# OK10xx_S_V1_1.net
KiCad netlist of a schematic drawn in Altium Designer
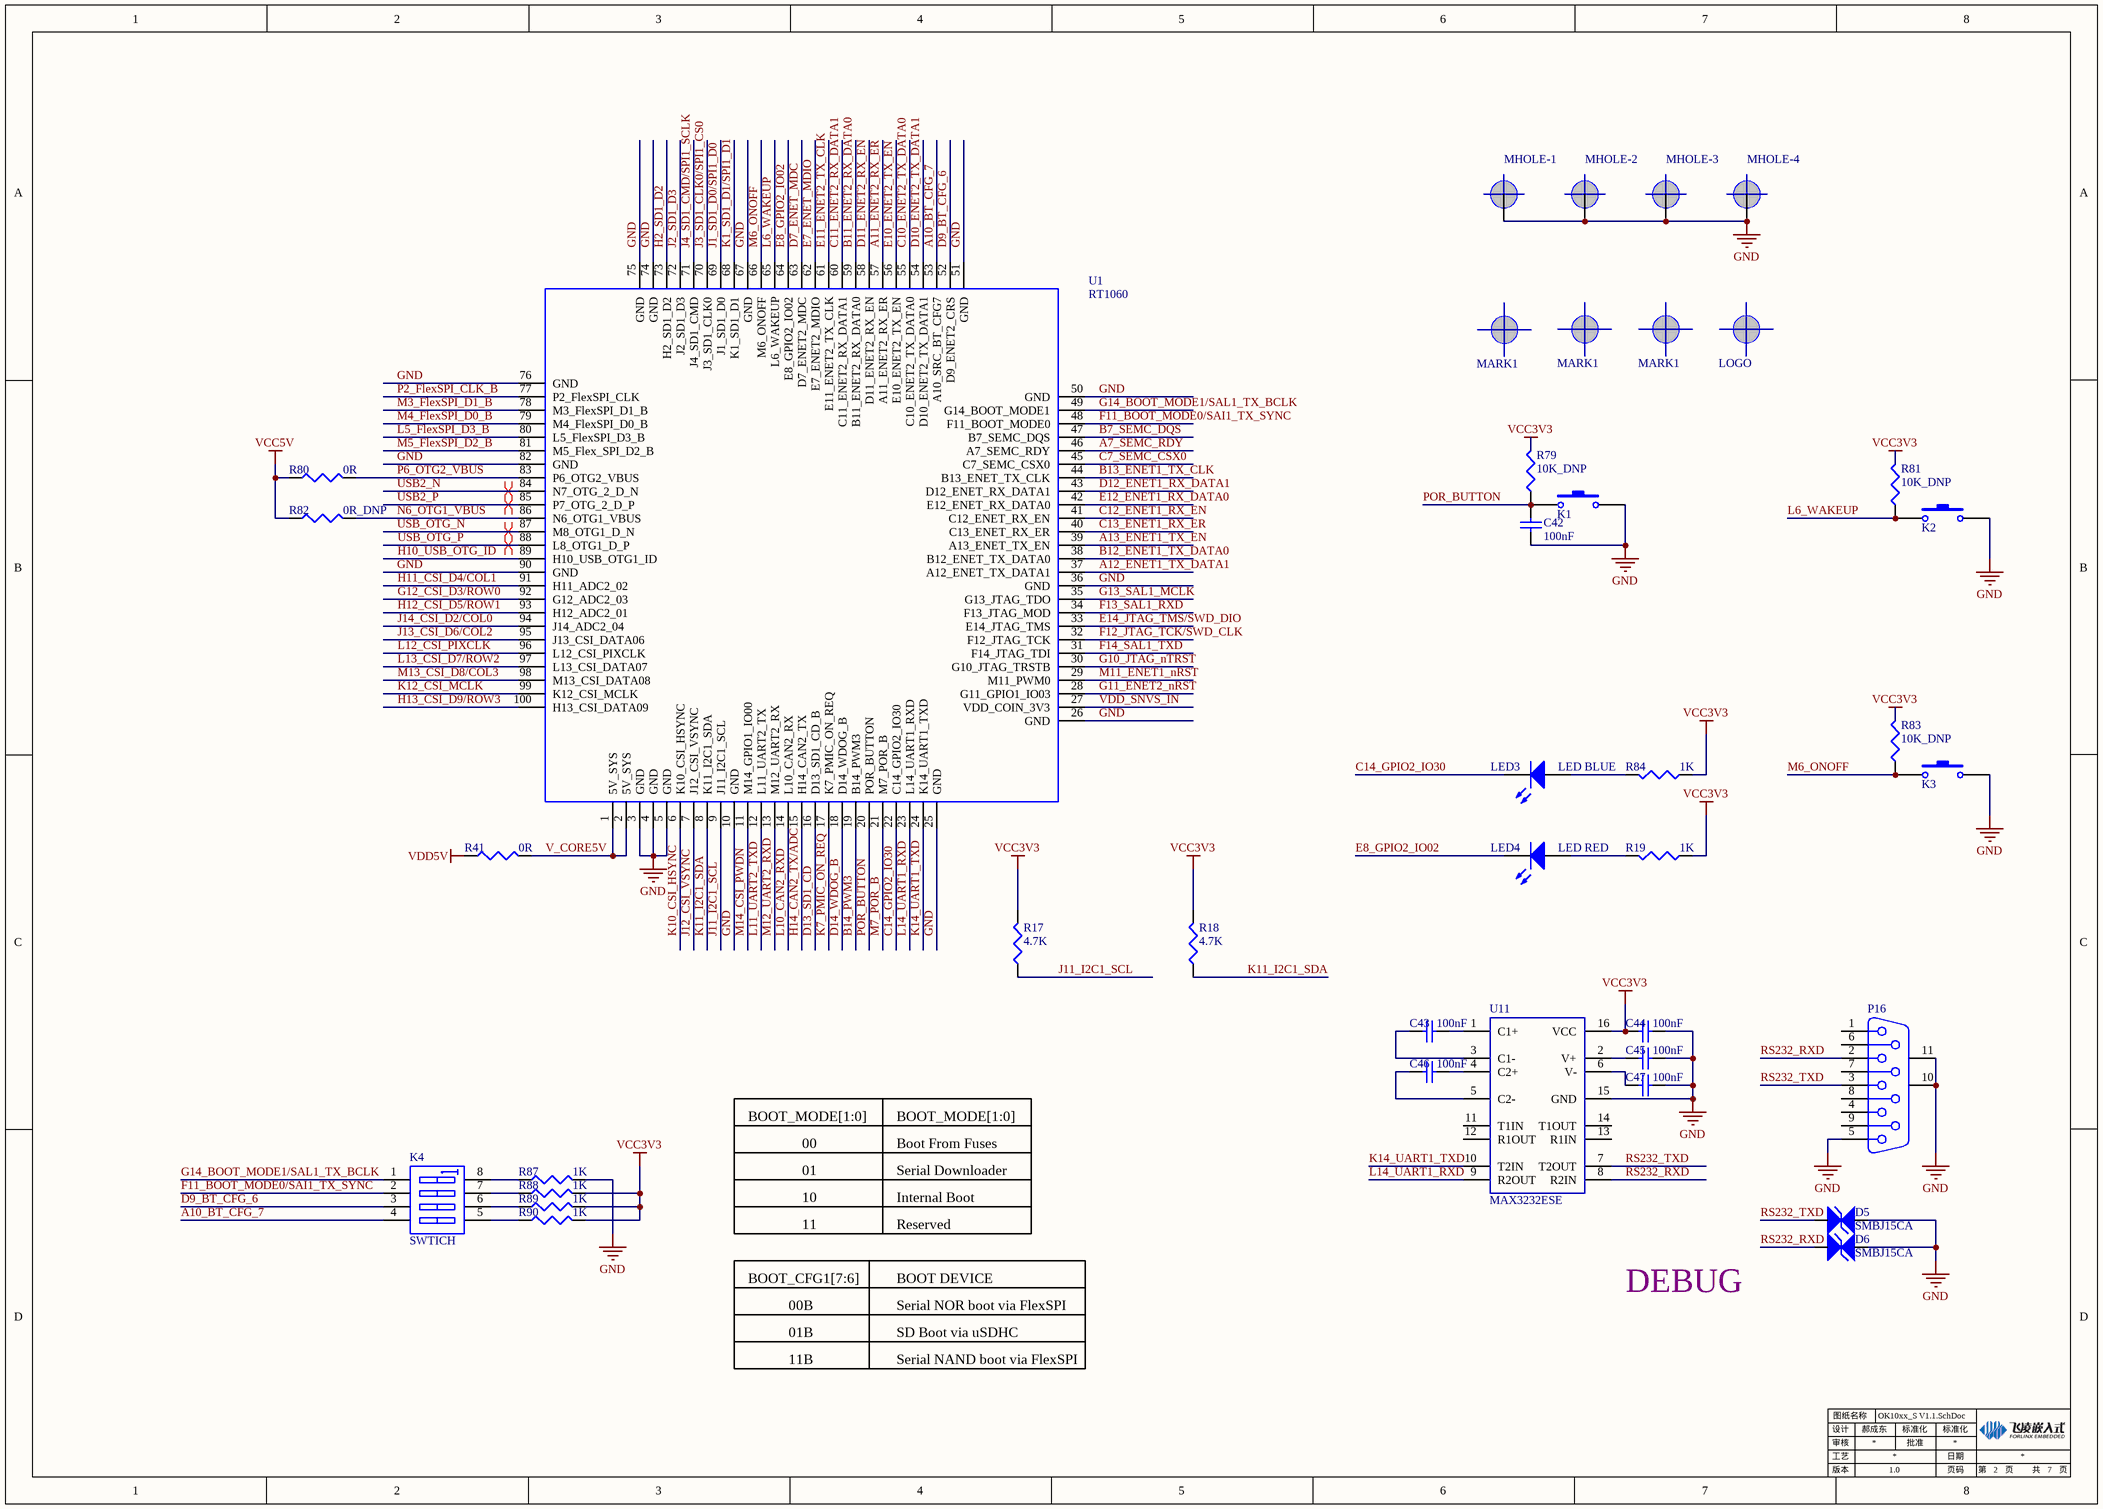
[diagram p0: OK10xx_S V1.1.SchDoc]

(export (version "E")
  (design (tool "Eeschema 10.0.6"))
  (components
    (comp (ref "C42")
      (value "100nF")
      (footprint "0603C+")
      (description "Capacitor")
      (fields (field (name "PUBLISHER") "Altium Limited"))
      (libsource (lib "RT1060") (part "Cap"))
    )
    (comp (ref "C43")
      (value "100nF")
      (footprint "0603C+")
      (description "Capacitor")
      (fields (field (name "PUBLISHER") "Altium Limited"))
      (libsource (lib "Miscellaneous Devices") (part "Cap"))
    )
    (comp (ref "C44")
      (value "100nF")
      (footprint "0603C+")
      (description "Capacitor")
      (fields (field (name "PUBLISHER") "Altium Limited"))
      (libsource (lib "Miscellaneous Devices") (part "Cap"))
    )
    (comp (ref "C45")
      (value "100nF")
      (footprint "0603C+")
      (description "Capacitor")
      (fields (field (name "PUBLISHER") "Altium Limited"))
      (libsource (lib "Miscellaneous Devices") (part "Cap"))
    )
    (comp (ref "C46")
      (value "100nF")
      (footprint "0603C+")
      (description "Capacitor")
      (fields (field (name "PUBLISHER") "Altium Limited"))
      (libsource (lib "Miscellaneous Devices") (part "Cap"))
    )
    (comp (ref "C47")
      (value "100nF")
      (footprint "0603C+")
      (description "Capacitor")
      (fields (field (name "PUBLISHER") "Altium Limited"))
      (libsource (lib "Miscellaneous Devices") (part "Cap"))
    )
    (comp (ref "D5") (value "SMBJ15CA") (footprint "SMB/DO-214AA") (libsource (lib "RT1060") (part "TVS")))
    (comp (ref "D6") (value "SMBJ15CA") (footprint "SMB/DO-214AA") (libsource (lib "RT1060") (part "TVS")))
    (comp (ref "K1")
      (value "6*6*5侧位2脚带支架")
      (description "Switch")
      (fields (field (name "PUBLISHER") "Altium Limited"))
      (libsource (lib "RT1060") (part "SW-PB"))
    )
    (comp (ref "K2")
      (value "6*6*5侧位2脚带支架")
      (description "Switch")
      (fields (field (name "PUBLISHER") "Altium Limited"))
      (libsource (lib "RT1060") (part "SW-PB"))
    )
    (comp (ref "K3")
      (value "6*6*5侧位2脚带支架")
      (description "Switch")
      (fields (field (name "PUBLISHER") "Altium Limited"))
      (libsource (lib "RT1060") (part "SW-PB"))
    )
    (comp (ref "K4") (value "SWTICH") (footprint "SMD_4") (libsource (lib "RT1060") (part "SWTICH_DIP6")))
    (comp (ref "LED3")
      (value "LED_BULE")
      (footprint "LED0603_M1608")
      (description "Typical RED, GREEN, YELLOW, AMBER GaAs LED")
      (fields (field (name "BOOK") "LED BLUE") (field (name "PUBLISHER") "Altium Limited"))
      (libsource (lib "RT1060") (part "LED2"))
    )
    (comp (ref "LED4")
      (value "LED_BULE")
      (footprint "LED0603_M1608")
      (description "Typical RED, GREEN, YELLOW, AMBER GaAs LED")
      (fields (field (name "BOOK") "LED RED") (field (name "PUBLISHER") "Altium Limited"))
      (libsource (lib "RT1060") (part "LED2"))
    )
    (comp (ref "LOGO1") (value "LOGO") (footprint "LOGO") (libsource (lib "RT1060") (part "MHOLE_1")))
    (comp (ref "M1") (value "MHOLE-1") (footprint "3.2mm_hole") (libsource (lib "RT1060") (part "MHOLE-2")))
    (comp (ref "M2") (value "MHOLE-2") (footprint "3.2mm_hole") (libsource (lib "RT1060") (part "MHOLE-2")))
    (comp (ref "M3") (value "MHOLE-3") (footprint "3.2mm_hole") (libsource (lib "RT1060") (part "MHOLE-2")))
    (comp (ref "M4") (value "MHOLE-4") (footprint "3.2mm_hole") (libsource (lib "RT1060") (part "MHOLE-2")))
    (comp (ref "Mark1") (value "MARK1") (footprint "MARK POINT") (libsource (lib "RT1060") (part "MHOLE")))
    (comp (ref "Mark2") (value "MARK1") (footprint "MARK POINT") (libsource (lib "RT1060") (part "MHOLE")))
    (comp (ref "Mark3") (value "MARK1") (footprint "MARK POINT") (libsource (lib "RT1060") (part "MHOLE")))
    (comp (ref "P16")
      (value "DEBUG")
      (footprint "DSUB1.385-2H9-M")
      (description "Receptacle Assembly, 9 Position, Right Angle")
      (fields (field (name "PUBLISHER") "Altium Limited"))
      (libsource (lib "RT1060") (part "D Connector 9"))
    )
    (comp (ref "R17")
      (value "4.7K")
      (footprint "0603R+")
      (description "Resistor")
      (fields (field (name "PUBLISHER") "Altium Limited"))
      (libsource (lib "Miscellaneous Devices") (part "Res3"))
    )
    (comp (ref "R18")
      (value "4.7K")
      (footprint "0603R+")
      (description "Resistor")
      (fields (field (name "PUBLISHER") "Altium Limited"))
      (libsource (lib "Miscellaneous Devices") (part "Res3"))
    )
    (comp (ref "R19")
      (value "1K")
      (footprint "0603R+")
      (description "Resistor")
      (fields (field (name "PUBLISHER") "Altium Limited"))
      (libsource (lib "RT1060") (part "Res3"))
    )
    (comp (ref "R41")
      (value "0R")
      (footprint "R_1210")
      (description "Resistor")
      (fields (field (name "PUBLISHER") "Altium Limited"))
      (libsource (lib "RT1060") (part "Res3"))
    )
    (comp (ref "R79")
      (value "10K_DNP")
      (footprint "0603R+")
      (description "Resistor")
      (fields (field (name "PUBLISHER") "Altium Limited"))
      (libsource (lib "RT1060") (part "Res3"))
    )
    (comp (ref "R80")
      (value "0R")
      (footprint "0603R+")
      (description "Resistor")
      (fields (field (name "PUBLISHER") "Altium Limited"))
      (libsource (lib "RT1060") (part "Res3"))
    )
    (comp (ref "R81")
      (value "10K_DNP")
      (footprint "0603R+")
      (description "Resistor")
      (fields (field (name "PUBLISHER") "Altium Limited"))
      (libsource (lib "RT1060") (part "Res3"))
    )
    (comp (ref "R82")
      (value "0R_DNP")
      (footprint "0603R+")
      (description "Resistor")
      (fields (field (name "PUBLISHER") "Altium Limited"))
      (libsource (lib "RT1060") (part "Res3"))
    )
    (comp (ref "R83")
      (value "10K_DNP")
      (footprint "0603R+")
      (description "Resistor")
      (fields (field (name "PUBLISHER") "Altium Limited"))
      (libsource (lib "RT1060") (part "Res3"))
    )
    (comp (ref "R84")
      (value "1K")
      (footprint "0603R+")
      (description "Resistor")
      (fields (field (name "PUBLISHER") "Altium Limited"))
      (libsource (lib "RT1060") (part "Res3"))
    )
    (comp (ref "R87")
      (value "1K")
      (footprint "0603R+")
      (description "Resistor")
      (fields (field (name "PUBLISHER") "Altium Limited"))
      (libsource (lib "RT1060") (part "Res3"))
    )
    (comp (ref "R88")
      (value "1K")
      (footprint "0603R+")
      (description "Resistor")
      (fields (field (name "PUBLISHER") "Altium Limited"))
      (libsource (lib "RT1060") (part "Res3"))
    )
    (comp (ref "R89")
      (value "1K")
      (footprint "0603R+")
      (description "Resistor")
      (fields (field (name "PUBLISHER") "Altium Limited"))
      (libsource (lib "RT1060") (part "Res3"))
    )
    (comp (ref "R90")
      (value "1K")
      (footprint "0603R+")
      (description "Resistor")
      (fields (field (name "PUBLISHER") "Altium Limited"))
      (libsource (lib "RT1060") (part "Res3"))
    )
    (comp (ref "U1") (value "RT1060") (libsource (lib "RT1060") (part "RT1060")))
    (comp (ref "U11") (value "MAX3232ESE") (footprint "SOIC-16N") (libsource (lib "RT1060") (part "MAX3232")))
  )
  (nets
    (net (code "1") (name "/A7_SEMC_RDY") (class "Default")
      (node (ref "U1") (pin "46") (pinfunction "A7_SEMC_RDY_46") (pintype "passive"))
    )
    (net (code "2") (name "/A10_BT_CFG_7") (class "Default")
      (node (ref "K4") (pin "4") (pinfunction "A4_4") (pintype "passive"))
      (node (ref "U1") (pin "53") (pinfunction "A10_SRC_BT_CFG7_53") (pintype "passive"))
    )
    (net (code "3") (name "/A11_ENET2_RX_ER") (class "Default")
      (node (ref "U1") (pin "57") (pinfunction "A11_ENET2_RX_ER_57") (pintype "passive"))
    )
    (net (code "4") (name "/A12_ENET1_TX_DATA1") (class "Default")
      (node (ref "U1") (pin "37") (pinfunction "A12_ENET_TX_DATA1_37") (pintype "passive"))
    )
    (net (code "5") (name "/A13_ENET1_TX_EN") (class "Default")
      (node (ref "U1") (pin "39") (pinfunction "A13_ENET_TX_EN_39") (pintype "passive"))
    )
    (net (code "6") (name "/B7_SEMC_DQS") (class "Default")
      (node (ref "U1") (pin "47") (pinfunction "B7_SEMC_DQS_47") (pintype "passive"))
    )
    (net (code "7") (name "/B11_ENET2_RX_DATA0") (class "Default")
      (node (ref "U1") (pin "59") (pinfunction "B11_ENET2_RX_DATA0_59") (pintype "passive"))
    )
    (net (code "8") (name "/B12_ENET1_TX_DATA0") (class "Default")
      (node (ref "U1") (pin "38") (pinfunction "B12_ENET_TX_DATA0_38") (pintype "passive"))
    )
    (net (code "9") (name "/B13_ENET1_TX_CLK") (class "Default")
      (node (ref "U1") (pin "44") (pinfunction "B13_ENET_TX_CLK_44") (pintype "passive"))
    )
    (net (code "10") (name "/B14_PWM3") (class "Default")
      (node (ref "U1") (pin "19") (pinfunction "B14_PWM3_19") (pintype "passive"))
    )
    (net (code "11") (name "/C7_SEMC_CSX0") (class "Default")
      (node (ref "U1") (pin "45") (pinfunction "C7_SEMC_CSX0_45") (pintype "passive"))
    )
    (net (code "12") (name "/C10_ENET2_TX_DATA0") (class "Default")
      (node (ref "U1") (pin "55") (pinfunction "C10_ENET2_TX_DATA0_55") (pintype "passive"))
    )
    (net (code "13") (name "/C11_ENET2_RX_DATA1") (class "Default")
      (node (ref "U1") (pin "60") (pinfunction "C11_ENET2_RX_DATA1_60") (pintype "passive"))
    )
    (net (code "14") (name "/C12_ENET1_RX_EN") (class "Default")
      (node (ref "U1") (pin "41") (pinfunction "C12_ENET_RX_EN_41") (pintype "passive"))
    )
    (net (code "15") (name "/C13_ENET1_RX_ER") (class "Default")
      (node (ref "U1") (pin "40") (pinfunction "C13_ENET_RX_ER_40") (pintype "passive"))
    )
    (net (code "16") (name "/C14_GPIO2_IO30") (class "Default")
      (node (ref "LED3") (pin "2") (pinfunction "K_2") (pintype "passive"))
      (node (ref "U1") (pin "22") (pinfunction "C14_GPIO2_IO30_22") (pintype "passive"))
    )
    (net (code "17") (name "/D7_ENET_MDC") (class "Default")
      (node (ref "U1") (pin "63") (pinfunction "D7_ENET2_MDC_63") (pintype "passive"))
    )
    (net (code "18") (name "/D9_BT_CFG_6") (class "Default")
      (node (ref "K4") (pin "3") (pinfunction "A3_3") (pintype "passive"))
      (node (ref "U1") (pin "52") (pinfunction "D9_ENET2_CRS_52") (pintype "passive"))
    )
    (net (code "19") (name "/D10_ENET2_TX_DATA1") (class "Default")
      (node (ref "U1") (pin "54") (pinfunction "D10_ENET2_TX_DATA1_54") (pintype "passive"))
    )
    (net (code "20") (name "/D11_ENET2_RX_EN") (class "Default")
      (node (ref "U1") (pin "58") (pinfunction "D11_ENET2_RX_EN_58") (pintype "passive"))
    )
    (net (code "21") (name "/D12_ENET1_RX_DATA1") (class "Default")
      (node (ref "U1") (pin "43") (pinfunction "D12_ENET_RX_DATA1_43") (pintype "passive"))
    )
    (net (code "22") (name "/D13_SD1_CD") (class "Default")
      (node (ref "U1") (pin "16") (pinfunction "D13_SD1_CD_B_16") (pintype "passive"))
    )
    (net (code "23") (name "/D14_WDOG_B") (class "Default")
      (node (ref "U1") (pin "18") (pinfunction "D14_WDOG_B_18") (pintype "passive"))
    )
    (net (code "24") (name "/E7_ENET_MDIO") (class "Default")
      (node (ref "U1") (pin "62") (pinfunction "E7_ENET2_MDIO_62") (pintype "passive"))
    )
    (net (code "25") (name "/E8_GPIO2_IO02") (class "Default")
      (node (ref "LED4") (pin "2") (pinfunction "K_2") (pintype "passive"))
      (node (ref "U1") (pin "64") (pinfunction "E8_GPIO2_IO02_64") (pintype "passive"))
    )
    (net (code "26") (name "/E10_ENET2_TX_EN") (class "Default")
      (node (ref "U1") (pin "56") (pinfunction "E10_ENET2_TX_EN_56") (pintype "passive"))
    )
    (net (code "27") (name "/E11_ENET2_TX_CLK") (class "Default")
      (node (ref "U1") (pin "61") (pinfunction "E11_ENET2_TX_CLK_61") (pintype "passive"))
    )
    (net (code "28") (name "/E12_ENET1_RX_DATA0") (class "Default")
      (node (ref "U1") (pin "42") (pinfunction "E12_ENET_RX_DATA0_42") (pintype "passive"))
    )
    (net (code "29") (name "/E14_JTAG_TMS{slash}SWD_DIO") (class "Default")
      (node (ref "U1") (pin "33") (pinfunction "E14_JTAG_TMS_33") (pintype "passive"))
    )
    (net (code "30") (name "/F11_BOOT_MODE0{slash}SAI1_TX_SYNC") (class "Default")
      (node (ref "K4") (pin "2") (pinfunction "A2_2") (pintype "passive"))
      (node (ref "U1") (pin "48") (pinfunction "F11_BOOT_MODE0_48") (pintype "passive"))
    )
    (net (code "31") (name "/F12_JTAG_TCK{slash}SWD_CLK") (class "Default")
      (node (ref "U1") (pin "32") (pinfunction "F12_JTAG_TCK_32") (pintype "passive"))
    )
    (net (code "32") (name "/F13_SAL1_RXD") (class "Default")
      (node (ref "U1") (pin "34") (pinfunction "F13_JTAG_MOD_34") (pintype "passive"))
    )
    (net (code "33") (name "/F14_SAL1_TXD") (class "Default")
      (node (ref "U1") (pin "31") (pinfunction "F14_JTAG_TDI_31") (pintype "passive"))
    )
    (net (code "34") (name "/G10_JTAG_nTRST") (class "Default")
      (node (ref "U1") (pin "30") (pinfunction "G10_JTAG_TRSTB_30") (pintype "passive"))
    )
    (net (code "35") (name "/G11_ENET2_nRST") (class "Default")
      (node (ref "U1") (pin "28") (pinfunction "G11_GPIO1_IO03_28") (pintype "passive"))
    )
    (net (code "36") (name "/G12_CSI_D3{slash}ROW0") (class "Default")
      (node (ref "U1") (pin "92") (pinfunction "G12_ADC2_03_92") (pintype "passive"))
    )
    (net (code "37") (name "/G13_SAL1_MCLK") (class "Default")
      (node (ref "U1") (pin "35") (pinfunction "G13_JTAG_TDO_35") (pintype "passive"))
    )
    (net (code "38") (name "/G14_BOOT_MODE1{slash}SAL1_TX_BCLK") (class "Default")
      (node (ref "K4") (pin "1") (pinfunction "A1_1") (pintype "passive"))
      (node (ref "U1") (pin "49") (pinfunction "G14_BOOT_MODE1_49") (pintype "passive"))
    )
    (net (code "39") (name "/H2_SD1_D2") (class "Default")
      (node (ref "U1") (pin "73") (pinfunction "H2_SD1_D2_73") (pintype "passive"))
    )
    (net (code "40") (name "/H10_USB_OTG_ID") (class "Default")
      (node (ref "U1") (pin "89") (pinfunction "H10_USB_OTG1_ID_89") (pintype "passive"))
    )
    (net (code "41") (name "/H11_CSI_D4{slash}COL1") (class "Default")
      (node (ref "U1") (pin "91") (pinfunction "H11_ADC2_02_91") (pintype "passive"))
    )
    (net (code "42") (name "/H12_CSI_D5{slash}ROW1") (class "Default")
      (node (ref "U1") (pin "93") (pinfunction "H12_ADC2_01_93") (pintype "passive"))
    )
    (net (code "43") (name "/H13_CSI_D9{slash}ROW3") (class "Default")
      (node (ref "U1") (pin "100") (pinfunction "H13_CSI_DATA09_100") (pintype "passive"))
    )
    (net (code "44") (name "/H14_CAN2_TX{slash}ADC") (class "Default")
      (node (ref "U1") (pin "15") (pinfunction "H14_CAN2_TX_15") (pintype "passive"))
    )
    (net (code "45") (name "/J1_SD1_D0{slash}SPI1_D0") (class "Default")
      (node (ref "U1") (pin "69") (pinfunction "J1_SD1_D0_69") (pintype "passive"))
    )
    (net (code "46") (name "/J2_SD1_D3") (class "Default")
      (node (ref "U1") (pin "72") (pinfunction "J2_SD1_D3_72") (pintype "passive"))
    )
    (net (code "47") (name "/J3_SD1_CLK0{slash}SPI1_CS0") (class "Default")
      (node (ref "U1") (pin "70") (pinfunction "J3_SD1_CLK0_70") (pintype "passive"))
    )
    (net (code "48") (name "/J4_SD1_CMD{slash}SPI1_SCLK") (class "Default")
      (node (ref "U1") (pin "71") (pinfunction "J4_SD1_CMD_71") (pintype "passive"))
    )
    (net (code "49") (name "/J11_I2C1_SCL") (class "Default")
      (node (ref "R17") (pin "1") (pinfunction "1_1") (pintype "passive"))
      (node (ref "U1") (pin "9") (pinfunction "J11_I2C1_SCL_9") (pintype "passive"))
    )
    (net (code "50") (name "/J12_CSI_VSYNC") (class "Default")
      (node (ref "U1") (pin "7") (pinfunction "J12_CSI_VSYNC_7") (pintype "passive"))
    )
    (net (code "51") (name "/J13_CSI_D6{slash}COL2") (class "Default")
      (node (ref "U1") (pin "95") (pinfunction "J13_CSI_DATA06_95") (pintype "passive"))
    )
    (net (code "52") (name "/J14_CSI_D2{slash}COL0") (class "Default")
      (node (ref "U1") (pin "94") (pinfunction "J14_ADC2_04_94") (pintype "passive"))
    )
    (net (code "53") (name "/K1_SD1_D1{slash}SPI1_D1") (class "Default")
      (node (ref "U1") (pin "68") (pinfunction "K1_SD1_D1_68") (pintype "passive"))
    )
    (net (code "54") (name "/K7_PMIC_ON_REQ") (class "Default")
      (node (ref "U1") (pin "17") (pinfunction "K7_PMIC_ON_REQ_17") (pintype "passive"))
    )
    (net (code "55") (name "/K10_CSI_HSYNC") (class "Default")
      (node (ref "U1") (pin "6") (pinfunction "K10_CSI_HSYNC_6") (pintype "passive"))
    )
    (net (code "56") (name "/K11_I2C1_SDA") (class "Default")
      (node (ref "R18") (pin "1") (pinfunction "1_1") (pintype "passive"))
      (node (ref "U1") (pin "8") (pinfunction "K11_I2C1_SDA_8") (pintype "passive"))
    )
    (net (code "57") (name "/K12_CSI_MCLK") (class "Default")
      (node (ref "U1") (pin "99") (pinfunction "K12_CSI_MCLK_99") (pintype "passive"))
    )
    (net (code "58") (name "/K14_UART1_TXD") (class "Default")
      (node (ref "U1") (pin "24") (pinfunction "K14_UART1_TXD_24") (pintype "passive"))
      (node (ref "U11") (pin "10") (pinfunction "T2IN_10") (pintype "passive"))
    )
    (net (code "59") (name "/L5_FlexSPI_D3_B") (class "Default")
      (node (ref "U1") (pin "80") (pinfunction "L5_FlexSPI_D3_B_80") (pintype "passive"))
    )
    (net (code "60") (name "/L6_WAKEUP") (class "Default")
      (node (ref "K2") (pin "1") (pinfunction "1_1") (pintype "passive"))
      (node (ref "R81") (pin "1") (pinfunction "1_1") (pintype "passive"))
      (node (ref "U1") (pin "65") (pinfunction "L6_WAKEUP_65") (pintype "passive"))
    )
    (net (code "61") (name "/L10_CAN2_RXD") (class "Default")
      (node (ref "U1") (pin "14") (pinfunction "L10_CAN2_RX_14") (pintype "passive"))
    )
    (net (code "62") (name "/L11_UART2_TXD") (class "Default")
      (node (ref "U1") (pin "12") (pinfunction "L11_UART2_TX_12") (pintype "passive"))
    )
    (net (code "63") (name "/L12_CSI_PIXCLK") (class "Default")
      (node (ref "U1") (pin "96") (pinfunction "L12_CSI_PIXCLK_96") (pintype "passive"))
    )
    (net (code "64") (name "/L13_CSI_D7{slash}ROW2") (class "Default")
      (node (ref "U1") (pin "97") (pinfunction "L13_CSI_DATA07_97") (pintype "passive"))
    )
    (net (code "65") (name "/L14_UART1_RXD") (class "Default")
      (node (ref "U1") (pin "23") (pinfunction "L14_UART1_RXD_23") (pintype "passive"))
      (node (ref "U11") (pin "9") (pinfunction "R2OUT_9") (pintype "passive"))
    )
    (net (code "66") (name "/M3_FlexSPI_D1_B") (class "Default")
      (node (ref "U1") (pin "78") (pinfunction "M3_FlexSPI_D1_B_78") (pintype "passive"))
    )
    (net (code "67") (name "/M4_FlexSPI_D0_B") (class "Default")
      (node (ref "U1") (pin "79") (pinfunction "M4_FlexSPI_D0_B_79") (pintype "passive"))
    )
    (net (code "68") (name "/M5_FlexSPI_D2_B") (class "Default")
      (node (ref "U1") (pin "81") (pinfunction "M5_Flex_SPI_D2_B_81") (pintype "passive"))
    )
    (net (code "69") (name "/M6_ONOFF") (class "Default")
      (node (ref "K3") (pin "1") (pinfunction "1_1") (pintype "passive"))
      (node (ref "R83") (pin "1") (pinfunction "1_1") (pintype "passive"))
      (node (ref "U1") (pin "66") (pinfunction "M6_ONOFF_66") (pintype "passive"))
    )
    (net (code "70") (name "/M7_POR_B") (class "Default")
      (node (ref "U1") (pin "21") (pinfunction "M7_POR_B_21") (pintype "passive"))
    )
    (net (code "71") (name "/M11_ENET1_nRST") (class "Default")
      (node (ref "U1") (pin "29") (pinfunction "M11_PWM0_29") (pintype "passive"))
    )
    (net (code "72") (name "/M12_UART2_RXD") (class "Default")
      (node (ref "U1") (pin "13") (pinfunction "M12_UART2_RX_13") (pintype "passive"))
    )
    (net (code "73") (name "/M13_CSI_D8{slash}COL3") (class "Default")
      (node (ref "U1") (pin "98") (pinfunction "M13_CSI_DATA08_98") (pintype "passive"))
    )
    (net (code "74") (name "/M14_CSI_PWDN") (class "Default")
      (node (ref "U1") (pin "11") (pinfunction "M14_GPIO1_IO00_11") (pintype "passive"))
    )
    (net (code "75") (name "/N6_OTG1_VBUS") (class "Default")
      (node (ref "R82") (pin "2") (pinfunction "2_2") (pintype "passive"))
      (node (ref "U1") (pin "86") (pinfunction "N6_OTG1_VBUS_86") (pintype "passive"))
    )
    (net (code "76") (name "/P2_FlexSPI_CLK_B") (class "Default")
      (node (ref "U1") (pin "77") (pinfunction "P2_FlexSPI_CLK_77") (pintype "passive"))
    )
    (net (code "77") (name "/P6_OTG2_VBUS") (class "Default")
      (node (ref "R80") (pin "2") (pinfunction "2_2") (pintype "passive"))
      (node (ref "U1") (pin "83") (pinfunction "P6_OTG2_VBUS_83") (pintype "passive"))
    )
    (net (code "78") (name "/POR_BUTTON") (class "Default")
      (node (ref "C42") (pin "2") (pinfunction "2_2") (pintype "passive"))
      (node (ref "K1") (pin "1") (pinfunction "1_1") (pintype "passive"))
      (node (ref "R79") (pin "1") (pinfunction "1_1") (pintype "passive"))
      (node (ref "U1") (pin "20") (pinfunction "POR_BUTTON_20") (pintype "passive"))
    )
    (net (code "79") (name "/RS232_RXD") (class "Default")
      (node (ref "D6") (pin "1") (pinfunction "1_1") (pintype "passive"))
      (node (ref "P16") (pin "2") (pinfunction "2_2") (pintype "passive"))
      (node (ref "U11") (pin "8") (pinfunction "R2IN_8") (pintype "passive"))
    )
    (net (code "80") (name "/RS232_TXD") (class "Default")
      (node (ref "D5") (pin "1") (pinfunction "1_1") (pintype "passive"))
      (node (ref "P16") (pin "3") (pinfunction "3_3") (pintype "passive"))
      (node (ref "U11") (pin "7") (pinfunction "T2OUT_7") (pintype "passive"))
    )
    (net (code "81") (name "/USB2_N") (class "Default")
      (node (ref "U1") (pin "84") (pinfunction "N7_OTG_2_D_N_84") (pintype "passive"))
    )
    (net (code "82") (name "/USB2_P") (class "Default")
      (node (ref "U1") (pin "85") (pinfunction "P7_OTG_2_D_P_85") (pintype "passive"))
    )
    (net (code "83") (name "/USB_OTG_N") (class "Default")
      (node (ref "U1") (pin "87") (pinfunction "M8_OTG1_D_N_87") (pintype "passive"))
    )
    (net (code "84") (name "/USB_OTG_P") (class "Default")
      (node (ref "U1") (pin "88") (pinfunction "L8_OTG1_D_P_88") (pintype "passive"))
    )
    (net (code "85") (name "/VDD_SNVS_IN") (class "Default")
      (node (ref "U1") (pin "27") (pinfunction "VDD_COIN_3V3_27") (pintype "passive"))
    )
    (net (code "86") (name "/V_CORE5V") (class "Default")
      (node (ref "R41") (pin "2") (pinfunction "2_2") (pintype "passive"))
      (node (ref "U1") (pin "1") (pinfunction "5V_SYS_1") (pintype "passive"))
      (node (ref "U1") (pin "2") (pinfunction "5V_SYS_2") (pintype "passive"))
    )
    (net (code "87") (name "GND") (class "Default")
      (node (ref "C42") (pin "1") (pinfunction "1_1") (pintype "passive"))
      (node (ref "C44") (pin "2") (pinfunction "2_2") (pintype "passive"))
      (node (ref "C45") (pin "2") (pinfunction "2_2") (pintype "passive"))
      (node (ref "C47") (pin "2") (pinfunction "2_2") (pintype "passive"))
      (node (ref "D5") (pin "2") (pinfunction "2_2") (pintype "passive"))
      (node (ref "D6") (pin "2") (pinfunction "2_2") (pintype "passive"))
      (node (ref "K1") (pin "2") (pinfunction "2_2") (pintype "passive"))
      (node (ref "K2") (pin "2") (pinfunction "2_2") (pintype "passive"))
      (node (ref "K3") (pin "2") (pinfunction "2_2") (pintype "passive"))
      (node (ref "M1") (pin "1") (pinfunction "EF_1") (pintype "passive"))
      (node (ref "M2") (pin "1") (pinfunction "EF_1") (pintype "passive"))
      (node (ref "M3") (pin "1") (pinfunction "EF_1") (pintype "passive"))
      (node (ref "M4") (pin "1") (pinfunction "EF_1") (pintype "passive"))
      (node (ref "P16") (pin "10") (pinfunction "MH1_10") (pintype "passive"))
      (node (ref "P16") (pin "11") (pinfunction "MH2_11") (pintype "passive"))
      (node (ref "P16") (pin "5") (pinfunction "5_5") (pintype "passive"))
      (node (ref "R87") (pin "2") (pinfunction "2_2") (pintype "passive"))
      (node (ref "U1") (pin "10") (pinfunction "GND_10") (pintype "passive"))
      (node (ref "U1") (pin "25") (pinfunction "GND_25") (pintype "passive"))
      (node (ref "U1") (pin "26") (pinfunction "GND_26") (pintype "passive"))
      (node (ref "U1") (pin "3") (pinfunction "GND_3") (pintype "passive"))
      (node (ref "U1") (pin "36") (pinfunction "GND_36") (pintype "passive"))
      (node (ref "U1") (pin "4") (pinfunction "GND_4") (pintype "passive"))
      (node (ref "U1") (pin "5") (pinfunction "GND_5") (pintype "passive"))
      (node (ref "U1") (pin "50") (pinfunction "GND_50") (pintype "passive"))
      (node (ref "U1") (pin "51") (pinfunction "GND_51") (pintype "passive"))
      (node (ref "U1") (pin "67") (pinfunction "GND_67") (pintype "passive"))
      (node (ref "U1") (pin "74") (pinfunction "GND_74") (pintype "passive"))
      (node (ref "U1") (pin "75") (pinfunction "GND_75") (pintype "passive"))
      (node (ref "U1") (pin "76") (pinfunction "GND_76") (pintype "passive"))
      (node (ref "U1") (pin "82") (pinfunction "GND_82") (pintype "passive"))
      (node (ref "U1") (pin "90") (pinfunction "GND_90") (pintype "passive"))
      (node (ref "U11") (pin "15") (pinfunction "GND_15") (pintype "passive"))
    )
    (net (code "88") (name "Net-(K4-B1)") (class "Default")
      (node (ref "K4") (pin "8") (pinfunction "B1_8") (pintype "passive"))
      (node (ref "R87") (pin "1") (pinfunction "1_1") (pintype "passive"))
    )
    (net (code "89") (name "Net-(K4-B2)") (class "Default")
      (node (ref "K4") (pin "7") (pinfunction "B2_7") (pintype "passive"))
      (node (ref "R88") (pin "1") (pinfunction "1_1") (pintype "passive"))
    )
    (net (code "90") (name "Net-(K4-B3)") (class "Default")
      (node (ref "K4") (pin "6") (pinfunction "B3_6") (pintype "passive"))
      (node (ref "R89") (pin "1") (pinfunction "1_1") (pintype "passive"))
    )
    (net (code "91") (name "Net-(K4-B4)") (class "Default")
      (node (ref "K4") (pin "5") (pinfunction "B4_5") (pintype "passive"))
      (node (ref "R90") (pin "1") (pinfunction "1_1") (pintype "passive"))
    )
    (net (code "92") (name "Net-(LED3-A)") (class "Default")
      (node (ref "LED3") (pin "1") (pinfunction "A_1") (pintype "passive"))
      (node (ref "R84") (pin "2") (pinfunction "2_2") (pintype "passive"))
    )
    (net (code "93") (name "Net-(LED4-A)") (class "Default")
      (node (ref "LED4") (pin "1") (pinfunction "A_1") (pintype "passive"))
      (node (ref "R19") (pin "2") (pinfunction "2_2") (pintype "passive"))
    )
    (net (code "94") (name "Net-(U11-C1+)") (class "Default")
      (node (ref "C43") (pin "2") (pinfunction "2_2") (pintype "passive"))
      (node (ref "U11") (pin "1") (pinfunction "C1+_1") (pintype "passive"))
    )
    (net (code "95") (name "Net-(U11-C1-)") (class "Default")
      (node (ref "C43") (pin "1") (pinfunction "1_1") (pintype "passive"))
      (node (ref "U11") (pin "3") (pinfunction "C1-_3") (pintype "passive"))
    )
    (net (code "96") (name "Net-(U11-C2+)") (class "Default")
      (node (ref "C46") (pin "2") (pinfunction "2_2") (pintype "passive"))
      (node (ref "U11") (pin "4") (pinfunction "C2+_4") (pintype "passive"))
    )
    (net (code "97") (name "Net-(U11-C2-)") (class "Default")
      (node (ref "C46") (pin "1") (pinfunction "1_1") (pintype "passive"))
      (node (ref "U11") (pin "5") (pinfunction "C2-_5") (pintype "passive"))
    )
    (net (code "98") (name "Net-(U11-V+)") (class "Default")
      (node (ref "C45") (pin "1") (pinfunction "1_1") (pintype "passive"))
      (node (ref "U11") (pin "2") (pinfunction "V+_2") (pintype "passive"))
    )
    (net (code "99") (name "Net-(U11-V-)") (class "Default")
      (node (ref "C47") (pin "1") (pinfunction "1_1") (pintype "passive"))
      (node (ref "U11") (pin "6") (pinfunction "V-_6") (pintype "passive"))
    )
    (net (code "100") (name "VCC3V3") (class "Default")
      (node (ref "C44") (pin "1") (pinfunction "1_1") (pintype "passive"))
      (node (ref "R17") (pin "2") (pinfunction "2_2") (pintype "passive"))
      (node (ref "R18") (pin "2") (pinfunction "2_2") (pintype "passive"))
      (node (ref "R19") (pin "1") (pinfunction "1_1") (pintype "passive"))
      (node (ref "R79") (pin "2") (pinfunction "2_2") (pintype "passive"))
      (node (ref "R81") (pin "2") (pinfunction "2_2") (pintype "passive"))
      (node (ref "R83") (pin "2") (pinfunction "2_2") (pintype "passive"))
      (node (ref "R84") (pin "1") (pinfunction "1_1") (pintype "passive"))
      (node (ref "R88") (pin "2") (pinfunction "2_2") (pintype "passive"))
      (node (ref "R89") (pin "2") (pinfunction "2_2") (pintype "passive"))
      (node (ref "R90") (pin "2") (pinfunction "2_2") (pintype "passive"))
      (node (ref "U11") (pin "16") (pinfunction "VCC_16") (pintype "passive"))
    )
    (net (code "101") (name "VCC5V") (class "Default")
      (node (ref "R80") (pin "1") (pinfunction "1_1") (pintype "passive"))
      (node (ref "R82") (pin "1") (pinfunction "1_1") (pintype "passive"))
    )
    (net (code "102") (name "VDD5V") (class "Default")
      (node (ref "R41") (pin "1") (pinfunction "1_1") (pintype "passive"))
    )
    (net (code "103") (name "unconnected-(P16-Pad1)") (class "Default")
      (node (ref "P16") (pin "1") (pinfunction "1_1") (pintype "passive"))
    )
    (net (code "104") (name "unconnected-(P16-Pad4)") (class "Default")
      (node (ref "P16") (pin "4") (pinfunction "4_4") (pintype "passive"))
    )
    (net (code "105") (name "unconnected-(P16-Pad6)") (class "Default")
      (node (ref "P16") (pin "6") (pinfunction "6_6") (pintype "passive"))
    )
    (net (code "106") (name "unconnected-(P16-Pad7)") (class "Default")
      (node (ref "P16") (pin "7") (pinfunction "7_7") (pintype "passive"))
    )
    (net (code "107") (name "unconnected-(P16-Pad8)") (class "Default")
      (node (ref "P16") (pin "8") (pinfunction "8_8") (pintype "passive"))
    )
    (net (code "108") (name "unconnected-(P16-Pad9)") (class "Default")
      (node (ref "P16") (pin "9") (pinfunction "9_9") (pintype "passive"))
    )
    (net (code "109") (name "unconnected-(U11-R1IN-Pad13)") (class "Default")
      (node (ref "U11") (pin "13") (pinfunction "R1IN_13") (pintype "passive"))
    )
    (net (code "110") (name "unconnected-(U11-R1OUT-Pad12)") (class "Default")
      (node (ref "U11") (pin "12") (pinfunction "R1OUT_12") (pintype "passive"))
    )
    (net (code "111") (name "unconnected-(U11-T1IN-Pad11)") (class "Default")
      (node (ref "U11") (pin "11") (pinfunction "T1IN_11") (pintype "passive"))
    )
    (net (code "112") (name "unconnected-(U11-T1OUT-Pad14)") (class "Default")
      (node (ref "U11") (pin "14") (pinfunction "T1OUT_14") (pintype "passive"))
    )
  )
)
